# dsd01-bsta.net
KiCad netlist of a schematic drawn in EAGLE
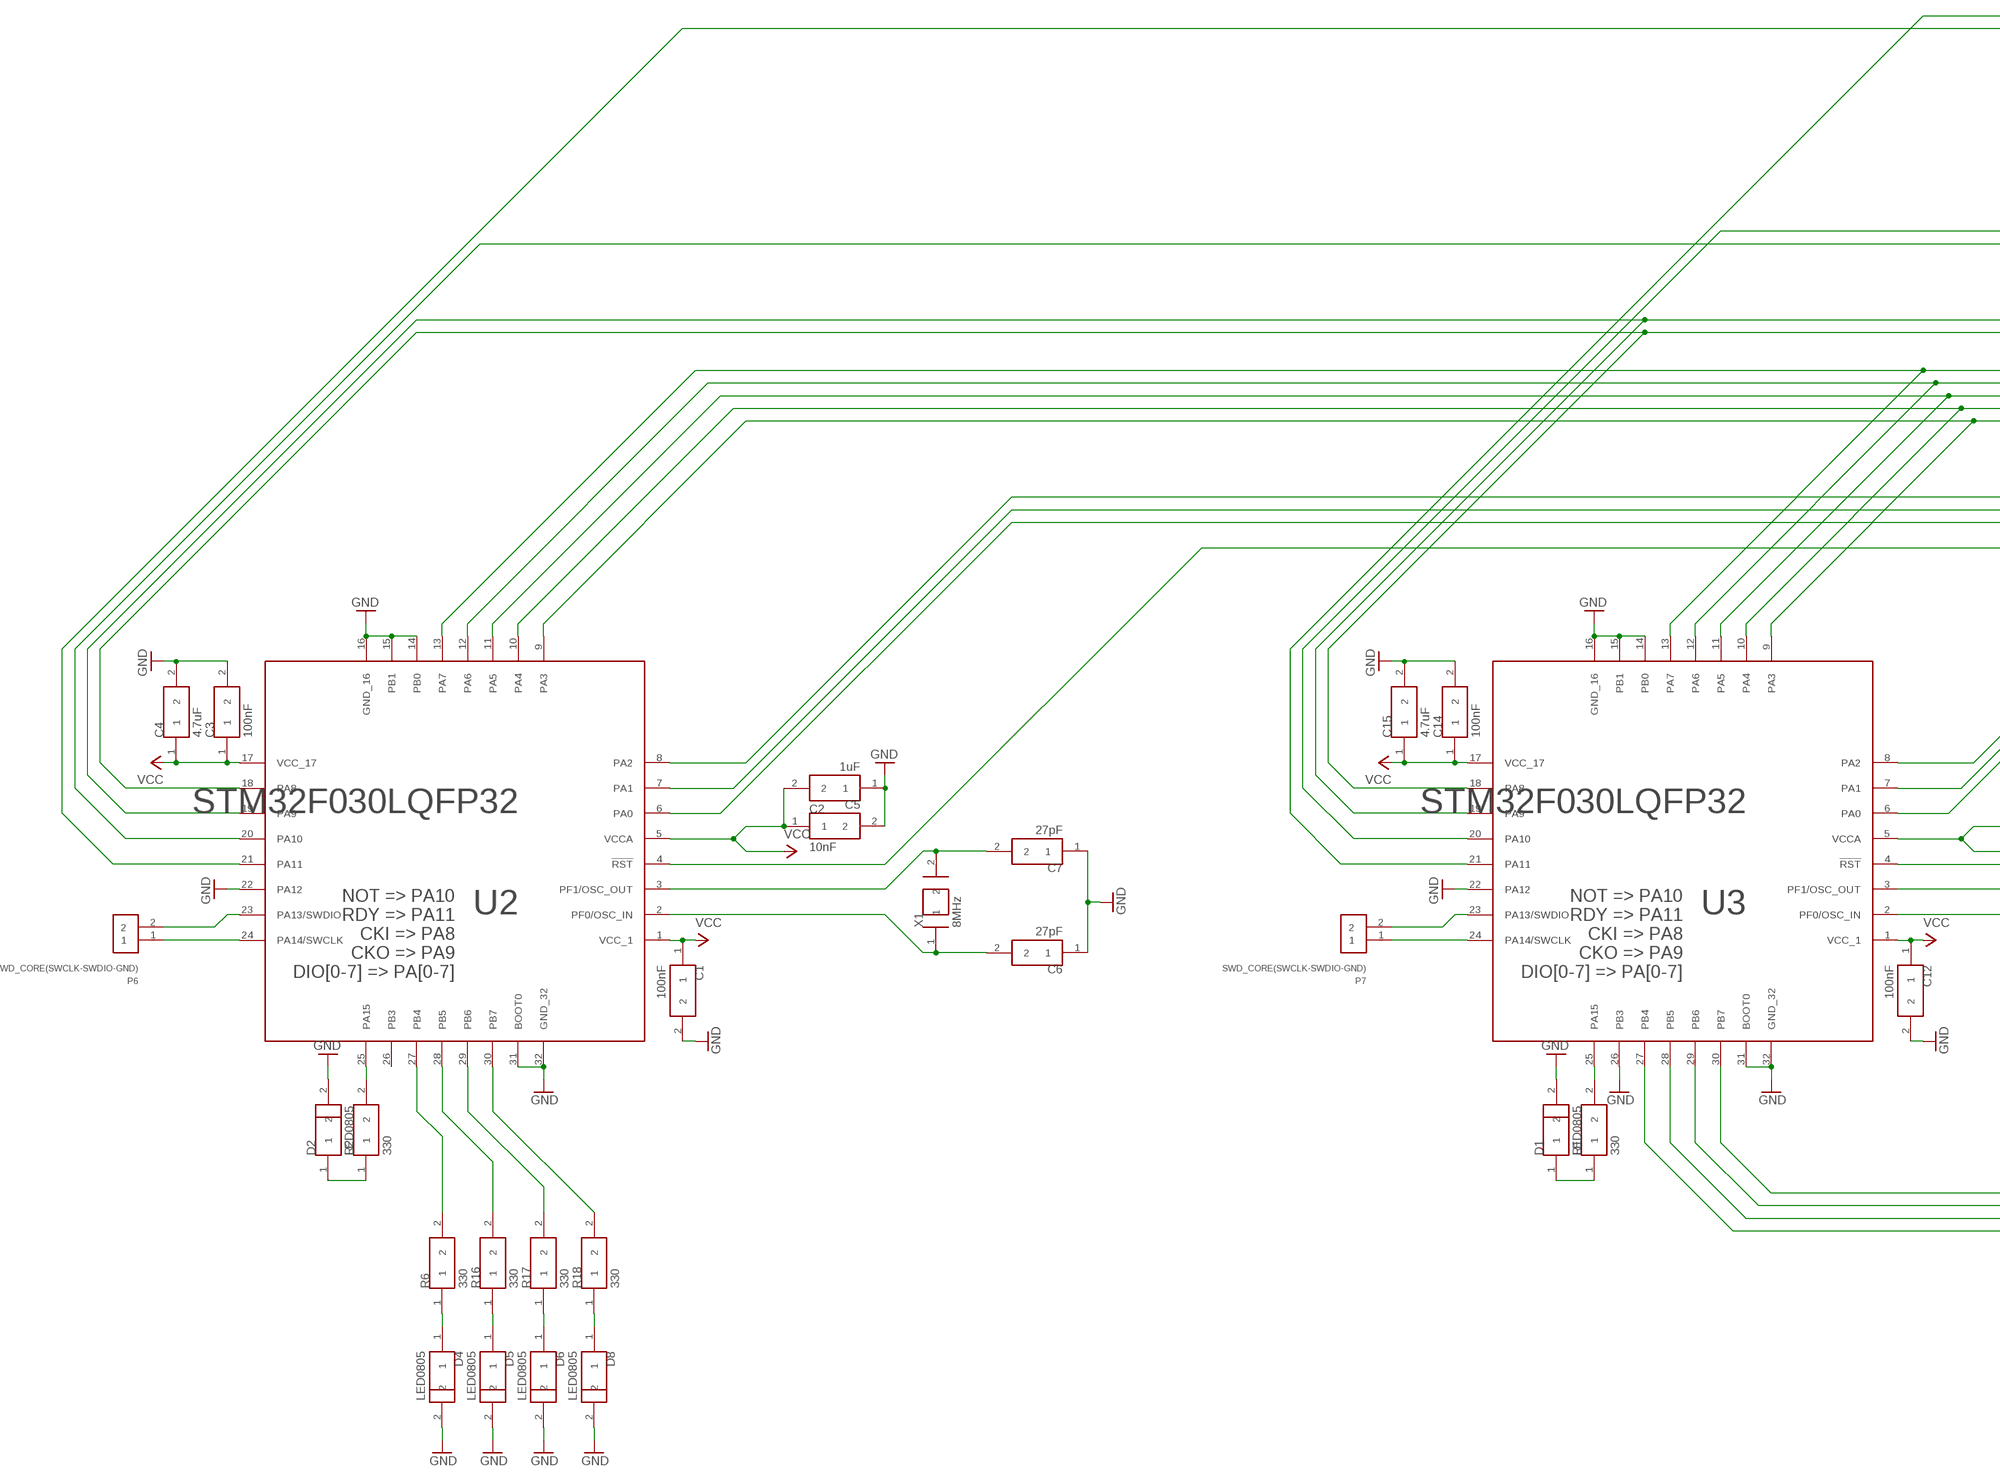
[diagram p0: schematic, sheet 1, part 1 of 2]
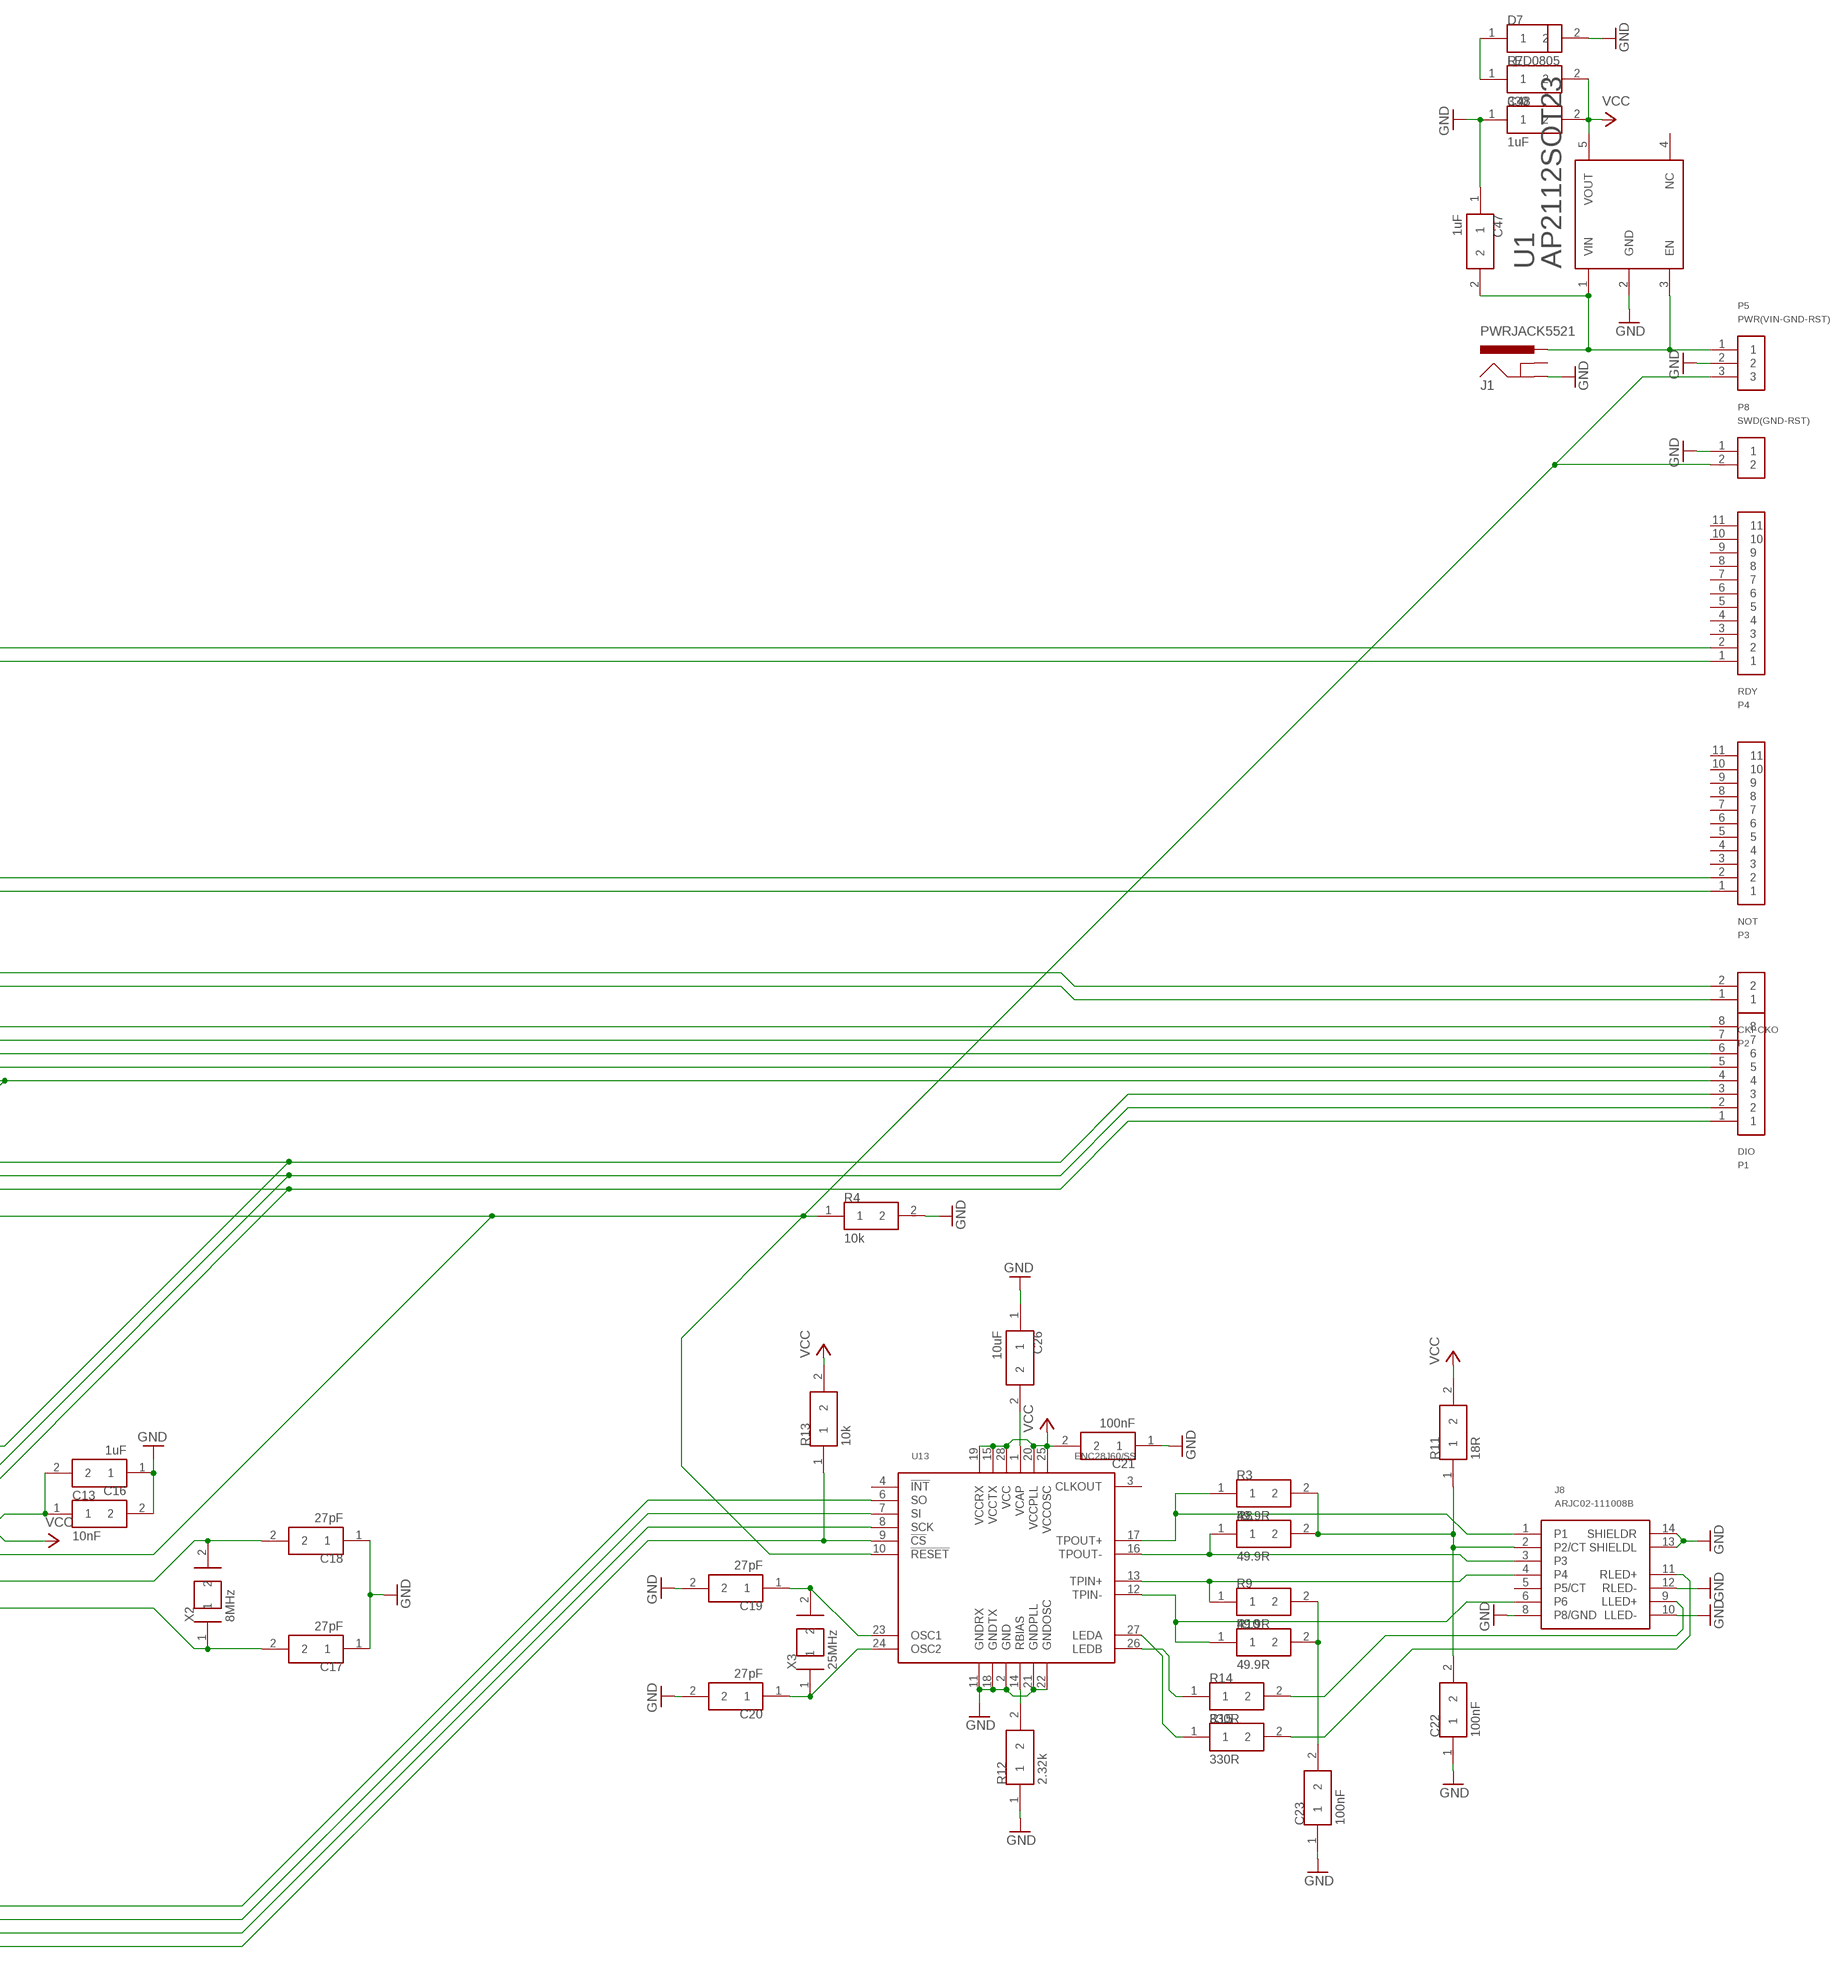
[diagram p1: schematic, sheet 1, part 2 of 2]

(export (version "E")
  (design (tool "Eeschema 10.0.6"))
  (components
    (comp (ref "C1")
      (value "100nF")
      (footprint "eagle-import:0805")
      (libsource (lib "eagle-import") (part "CAP0805"))
    )
    (comp (ref "C2")
      (value "10nF")
      (footprint "eagle-import:0805")
      (libsource (lib "eagle-import") (part "CAP0805"))
    )
    (comp (ref "C3")
      (value "100nF")
      (footprint "eagle-import:0805")
      (libsource (lib "eagle-import") (part "CAP0805"))
    )
    (comp (ref "C4")
      (value "4.7uF")
      (footprint "eagle-import:0805")
      (libsource (lib "eagle-import") (part "CAP0805"))
    )
    (comp (ref "C5")
      (value "1uF")
      (footprint "eagle-import:0805")
      (libsource (lib "eagle-import") (part "CAP0805"))
    )
    (comp (ref "C6")
      (value "27pF")
      (footprint "eagle-import:0805")
      (libsource (lib "eagle-import") (part "CAP0805"))
    )
    (comp (ref "C7")
      (value "27pF")
      (footprint "eagle-import:0805")
      (libsource (lib "eagle-import") (part "CAP0805"))
    )
    (comp (ref "C12")
      (value "100nF")
      (footprint "eagle-import:0805")
      (libsource (lib "eagle-import") (part "CAP0805"))
    )
    (comp (ref "C13")
      (value "10nF")
      (footprint "eagle-import:0805")
      (libsource (lib "eagle-import") (part "CAP0805"))
    )
    (comp (ref "C14")
      (value "100nF")
      (footprint "eagle-import:0805")
      (libsource (lib "eagle-import") (part "CAP0805"))
    )
    (comp (ref "C15")
      (value "4.7uF")
      (footprint "eagle-import:0805")
      (libsource (lib "eagle-import") (part "CAP0805"))
    )
    (comp (ref "C16")
      (value "1uF")
      (footprint "eagle-import:0805")
      (libsource (lib "eagle-import") (part "CAP0805"))
    )
    (comp (ref "C17")
      (value "27pF")
      (footprint "eagle-import:0805")
      (libsource (lib "eagle-import") (part "CAP0805"))
    )
    (comp (ref "C18")
      (value "27pF")
      (footprint "eagle-import:0805")
      (libsource (lib "eagle-import") (part "CAP0805"))
    )
    (comp (ref "C19")
      (value "27pF")
      (footprint "eagle-import:0805")
      (libsource (lib "eagle-import") (part "CAP0805"))
    )
    (comp (ref "C20")
      (value "27pF")
      (footprint "eagle-import:0805")
      (libsource (lib "eagle-import") (part "CAP0805"))
    )
    (comp (ref "C21")
      (value "100nF")
      (footprint "eagle-import:0805")
      (libsource (lib "eagle-import") (part "CAP0805"))
    )
    (comp (ref "C22")
      (value "100nF")
      (footprint "eagle-import:0805")
      (libsource (lib "eagle-import") (part "CAP0805"))
    )
    (comp (ref "C23")
      (value "100nF")
      (footprint "eagle-import:0805")
      (libsource (lib "eagle-import") (part "CAP0805"))
    )
    (comp (ref "C26")
      (value "10uF")
      (footprint "eagle-import:0805")
      (libsource (lib "eagle-import") (part "CAP0805"))
    )
    (comp (ref "C47")
      (value "1uF")
      (footprint "eagle-import:0805")
      (libsource (lib "eagle-import") (part "CAP0805"))
    )
    (comp (ref "C48")
      (value "1uF")
      (footprint "eagle-import:0805")
      (libsource (lib "eagle-import") (part "CAP0805"))
    )
    (comp (ref "D1")
      (value "LED0805")
      (footprint "eagle-import:0805")
      (libsource (lib "eagle-import") (part "LED0805"))
    )
    (comp (ref "D2")
      (value "LED0805")
      (footprint "eagle-import:0805")
      (libsource (lib "eagle-import") (part "LED0805"))
    )
    (comp (ref "D4")
      (value "LED0805")
      (footprint "eagle-import:0805")
      (libsource (lib "eagle-import") (part "LED0805"))
    )
    (comp (ref "D5")
      (value "LED0805")
      (footprint "eagle-import:0805")
      (libsource (lib "eagle-import") (part "LED0805"))
    )
    (comp (ref "D6")
      (value "LED0805")
      (footprint "eagle-import:0805")
      (libsource (lib "eagle-import") (part "LED0805"))
    )
    (comp (ref "D7")
      (value "LED0805")
      (footprint "eagle-import:0805")
      (libsource (lib "eagle-import") (part "LED0805"))
    )
    (comp (ref "D8")
      (value "LED0805")
      (footprint "eagle-import:0805")
      (libsource (lib "eagle-import") (part "LED0805"))
    )
    (comp (ref "J1")
      (value "PWRJACK5521")
      (footprint "eagle-import:PWRJACK_5521")
      (libsource (lib "eagle-import") (part "PWRJACK5521"))
    )
    (comp (ref "J8")
      (value "ARJC02-111008B")
      (footprint "eagle-import:ARJC02-111008B")
      (libsource (lib "eagle-import") (part "ARJC02-111008B"))
    )
    (comp (ref "P1")
      (value "DIO")
      (footprint "eagle-import:PIN_8")
      (libsource (lib "eagle-import") (part "PIN_8"))
    )
    (comp (ref "P2")
      (value "CKI-CKO")
      (footprint "eagle-import:PIN_2")
      (libsource (lib "eagle-import") (part "PIN_2"))
    )
    (comp (ref "P3")
      (value "NOT")
      (footprint "eagle-import:PIN_11")
      (libsource (lib "eagle-import") (part "PIN_11"))
    )
    (comp (ref "P4")
      (value "RDY")
      (footprint "eagle-import:PIN_11")
      (libsource (lib "eagle-import") (part "PIN_11"))
    )
    (comp (ref "P5")
      (value "PWR(VIN-GND-RST)")
      (footprint "eagle-import:PIN_3")
      (libsource (lib "eagle-import") (part "PIN_3"))
    )
    (comp (ref "P6")
      (value "SWD_CORE(SWCLK-SWDIO-GND)")
      (footprint "eagle-import:PIN_2")
      (libsource (lib "eagle-import") (part "PIN_2"))
    )
    (comp (ref "P7")
      (value "SWD_CORE(SWCLK-SWDIO-GND)")
      (footprint "eagle-import:PIN_2")
      (libsource (lib "eagle-import") (part "PIN_2"))
    )
    (comp (ref "P8")
      (value "SWD(GND-RST)")
      (footprint "eagle-import:PIN_2")
      (libsource (lib "eagle-import") (part "PIN_2"))
    )
    (comp (ref "R1")
      (value "330")
      (footprint "eagle-import:0805")
      (libsource (lib "eagle-import") (part "RES0805"))
    )
    (comp (ref "R2")
      (value "330")
      (footprint "eagle-import:0805")
      (libsource (lib "eagle-import") (part "RES0805"))
    )
    (comp (ref "R3")
      (value "49.9R")
      (footprint "eagle-import:0805")
      (libsource (lib "eagle-import") (part "RES0805"))
    )
    (comp (ref "R4")
      (value "10k")
      (footprint "eagle-import:0805")
      (libsource (lib "eagle-import") (part "RES0805"))
    )
    (comp (ref "R6")
      (value "330")
      (footprint "eagle-import:0805")
      (libsource (lib "eagle-import") (part "RES0805"))
    )
    (comp (ref "R7")
      (value "330")
      (footprint "eagle-import:0805")
      (libsource (lib "eagle-import") (part "RES0805"))
    )
    (comp (ref "R8")
      (value "49.9R")
      (footprint "eagle-import:0805")
      (libsource (lib "eagle-import") (part "RES0805"))
    )
    (comp (ref "R9")
      (value "49.9R")
      (footprint "eagle-import:0805")
      (libsource (lib "eagle-import") (part "RES0805"))
    )
    (comp (ref "R10")
      (value "49.9R")
      (footprint "eagle-import:0805")
      (libsource (lib "eagle-import") (part "RES0805"))
    )
    (comp (ref "R11")
      (value "18R")
      (footprint "eagle-import:0805")
      (libsource (lib "eagle-import") (part "RES0805"))
    )
    (comp (ref "R12")
      (value "2.32k")
      (footprint "eagle-import:0805")
      (libsource (lib "eagle-import") (part "RES0805"))
    )
    (comp (ref "R13")
      (value "10k")
      (footprint "eagle-import:0805")
      (libsource (lib "eagle-import") (part "RES0805"))
    )
    (comp (ref "R14")
      (value "330R")
      (footprint "eagle-import:0805")
      (libsource (lib "eagle-import") (part "RES0805"))
    )
    (comp (ref "R15")
      (value "330R")
      (footprint "eagle-import:0805")
      (libsource (lib "eagle-import") (part "RES0805"))
    )
    (comp (ref "R16")
      (value "330")
      (footprint "eagle-import:0805")
      (libsource (lib "eagle-import") (part "RES0805"))
    )
    (comp (ref "R17")
      (value "330")
      (footprint "eagle-import:0805")
      (libsource (lib "eagle-import") (part "RES0805"))
    )
    (comp (ref "R18")
      (value "330")
      (footprint "eagle-import:0805")
      (libsource (lib "eagle-import") (part "RES0805"))
    )
    (comp (ref "U1")
      (value "AP2112SOT23")
      (footprint "eagle-import:SOT23-5")
      (libsource (lib "eagle-import") (part "AP2112SOT23"))
    )
    (comp (ref "U2")
      (value "STM32F030LQFP32")
      (footprint "eagle-import:QFP32")
      (libsource (lib "eagle-import") (part "STM32F030LQFP32"))
    )
    (comp (ref "U3")
      (value "STM32F030LQFP32")
      (footprint "eagle-import:QFP32")
      (libsource (lib "eagle-import") (part "STM32F030LQFP32"))
    )
    (comp (ref "U13")
      (value "ENC28J60/SS")
      (footprint "eagle-import:SSOP28")
      (libsource (lib "eagle-import") (part "ENC28J60/SS"))
    )
    (comp (ref "X1")
      (value "8MHz")
      (footprint "eagle-import:XTAL_532")
      (libsource (lib "eagle-import") (part "XTALSMD-5X32"))
    )
    (comp (ref "X2")
      (value "8MHz")
      (footprint "eagle-import:XTAL_532")
      (libsource (lib "eagle-import") (part "XTALSMD-5X32"))
    )
    (comp (ref "X3")
      (value "25MHz")
      (footprint "eagle-import:XTAL_532")
      (libsource (lib "eagle-import") (part "XTALSMD-5X32"))
    )
  )
  (nets
    (net (code "1") (name "GND") (class "Default")
      (node (ref "C1") (pin "2") (pinfunction "2_2") (pintype "bidirectional"))
      (node (ref "C12") (pin "2") (pinfunction "2_2") (pintype "bidirectional"))
      (node (ref "C13") (pin "2") (pinfunction "2_2") (pintype "bidirectional"))
      (node (ref "C14") (pin "2") (pinfunction "2_2") (pintype "bidirectional"))
      (node (ref "C15") (pin "2") (pinfunction "2_2") (pintype "bidirectional"))
      (node (ref "C16") (pin "1") (pinfunction "1_1") (pintype "bidirectional"))
      (node (ref "C17") (pin "1") (pinfunction "1_1") (pintype "bidirectional"))
      (node (ref "C18") (pin "1") (pinfunction "1_1") (pintype "bidirectional"))
      (node (ref "C19") (pin "2") (pinfunction "2_2") (pintype "bidirectional"))
      (node (ref "C2") (pin "2") (pinfunction "2_2") (pintype "bidirectional"))
      (node (ref "C20") (pin "2") (pinfunction "2_2") (pintype "bidirectional"))
      (node (ref "C21") (pin "1") (pinfunction "1_1") (pintype "bidirectional"))
      (node (ref "C22") (pin "1") (pinfunction "1_1") (pintype "bidirectional"))
      (node (ref "C23") (pin "1") (pinfunction "1_1") (pintype "bidirectional"))
      (node (ref "C26") (pin "1") (pinfunction "1_1") (pintype "bidirectional"))
      (node (ref "C3") (pin "2") (pinfunction "2_2") (pintype "bidirectional"))
      (node (ref "C4") (pin "2") (pinfunction "2_2") (pintype "bidirectional"))
      (node (ref "C47") (pin "1") (pinfunction "1_1") (pintype "bidirectional"))
      (node (ref "C48") (pin "1") (pinfunction "1_1") (pintype "bidirectional"))
      (node (ref "C5") (pin "1") (pinfunction "1_1") (pintype "bidirectional"))
      (node (ref "C6") (pin "1") (pinfunction "1_1") (pintype "bidirectional"))
      (node (ref "C7") (pin "1") (pinfunction "1_1") (pintype "bidirectional"))
      (node (ref "D1") (pin "2") (pinfunction "2_2") (pintype "bidirectional"))
      (node (ref "D2") (pin "2") (pinfunction "2_2") (pintype "bidirectional"))
      (node (ref "D4") (pin "2") (pinfunction "2_2") (pintype "bidirectional"))
      (node (ref "D5") (pin "2") (pinfunction "2_2") (pintype "bidirectional"))
      (node (ref "D6") (pin "2") (pinfunction "2_2") (pintype "bidirectional"))
      (node (ref "D7") (pin "2") (pinfunction "2_2") (pintype "bidirectional"))
      (node (ref "D8") (pin "2") (pinfunction "2_2") (pintype "bidirectional"))
      (node (ref "J1") (pin "GND") (pinfunction "GND_GND") (pintype "bidirectional"))
      (node (ref "J8") (pin "10") (pinfunction "LLED-_10") (pintype "bidirectional"))
      (node (ref "J8") (pin "12") (pinfunction "RLED-_12") (pintype "bidirectional"))
      (node (ref "J8") (pin "13") (pinfunction "SHIELDL_13") (pintype "bidirectional"))
      (node (ref "J8") (pin "14") (pinfunction "SHIELDR_14") (pintype "bidirectional"))
      (node (ref "J8") (pin "8") (pinfunction "P8/GND_8") (pintype "bidirectional"))
      (node (ref "P5") (pin "2") (pinfunction "2_2") (pintype "bidirectional"))
      (node (ref "P8") (pin "1") (pinfunction "1_1") (pintype "bidirectional"))
      (node (ref "R12") (pin "1") (pinfunction "1_1") (pintype "bidirectional"))
      (node (ref "R4") (pin "2") (pinfunction "2_2") (pintype "bidirectional"))
      (node (ref "U1") (pin "2") (pinfunction "GND_2") (pintype "bidirectional"))
      (node (ref "U13") (pin "11") (pinfunction "GNDRX_11") (pintype "bidirectional"))
      (node (ref "U13") (pin "18") (pinfunction "GNDTX_18") (pintype "bidirectional"))
      (node (ref "U13") (pin "2") (pinfunction "GND_2") (pintype "bidirectional"))
      (node (ref "U13") (pin "21") (pinfunction "GNDPLL_21") (pintype "bidirectional"))
      (node (ref "U13") (pin "22") (pinfunction "GNDOSC_22") (pintype "bidirectional"))
      (node (ref "U2") (pin "14") (pinfunction "PB0_14") (pintype "bidirectional"))
      (node (ref "U2") (pin "15") (pinfunction "PB1_15") (pintype "bidirectional"))
      (node (ref "U2") (pin "16") (pinfunction "GND_16_16") (pintype "bidirectional"))
      (node (ref "U2") (pin "22") (pinfunction "PA12_22") (pintype "bidirectional"))
      (node (ref "U2") (pin "31") (pinfunction "BOOT0_31") (pintype "bidirectional"))
      (node (ref "U2") (pin "32") (pinfunction "GND_32_32") (pintype "bidirectional"))
      (node (ref "U3") (pin "14") (pinfunction "PB0_14") (pintype "bidirectional"))
      (node (ref "U3") (pin "15") (pinfunction "PB1_15") (pintype "bidirectional"))
      (node (ref "U3") (pin "16") (pinfunction "GND_16_16") (pintype "bidirectional"))
      (node (ref "U3") (pin "22") (pinfunction "PA12_22") (pintype "bidirectional"))
      (node (ref "U3") (pin "26") (pinfunction "PB3_26") (pintype "bidirectional"))
      (node (ref "U3") (pin "31") (pinfunction "BOOT0_31") (pintype "bidirectional"))
      (node (ref "U3") (pin "32") (pinfunction "GND_32_32") (pintype "bidirectional"))
    )
    (net (code "2") (name "Net-(C23-Pad2)") (class "Default")
      (node (ref "C23") (pin "2") (pinfunction "2_2") (pintype "bidirectional"))
      (node (ref "R10") (pin "2") (pinfunction "2_2") (pintype "bidirectional"))
      (node (ref "R9") (pin "2") (pinfunction "2_2") (pintype "bidirectional"))
    )
    (net (code "3") (name "Net-(D1-Pad1)") (class "Default")
      (node (ref "D1") (pin "1") (pinfunction "1_1") (pintype "bidirectional"))
      (node (ref "R1") (pin "1") (pinfunction "1_1") (pintype "bidirectional"))
    )
    (net (code "4") (name "Net-(D2-Pad1)") (class "Default")
      (node (ref "D2") (pin "1") (pinfunction "1_1") (pintype "bidirectional"))
      (node (ref "R2") (pin "1") (pinfunction "1_1") (pintype "bidirectional"))
    )
    (net (code "5") (name "Net-(D4-Pad1)") (class "Default")
      (node (ref "D4") (pin "1") (pinfunction "1_1") (pintype "bidirectional"))
      (node (ref "R6") (pin "1") (pinfunction "1_1") (pintype "bidirectional"))
    )
    (net (code "6") (name "Net-(D5-Pad1)") (class "Default")
      (node (ref "D5") (pin "1") (pinfunction "1_1") (pintype "bidirectional"))
      (node (ref "R16") (pin "1") (pinfunction "1_1") (pintype "bidirectional"))
    )
    (net (code "7") (name "Net-(D6-Pad1)") (class "Default")
      (node (ref "D6") (pin "1") (pinfunction "1_1") (pintype "bidirectional"))
      (node (ref "R17") (pin "1") (pinfunction "1_1") (pintype "bidirectional"))
    )
    (net (code "8") (name "Net-(D7-Pad1)") (class "Default")
      (node (ref "D7") (pin "1") (pinfunction "1_1") (pintype "bidirectional"))
      (node (ref "R7") (pin "1") (pinfunction "1_1") (pintype "bidirectional"))
    )
    (net (code "9") (name "Net-(D8-Pad1)") (class "Default")
      (node (ref "D8") (pin "1") (pinfunction "1_1") (pintype "bidirectional"))
      (node (ref "R18") (pin "1") (pinfunction "1_1") (pintype "bidirectional"))
    )
    (net (code "10") (name "Net-(J8-LLED+)") (class "Default")
      (node (ref "J8") (pin "9") (pinfunction "LLED+_9") (pintype "bidirectional"))
      (node (ref "R14") (pin "2") (pinfunction "2_2") (pintype "bidirectional"))
    )
    (net (code "11") (name "Net-(J8-P1)") (class "Default")
      (node (ref "J8") (pin "1") (pinfunction "P1_1") (pintype "bidirectional"))
      (node (ref "R3") (pin "1") (pinfunction "1_1") (pintype "bidirectional"))
      (node (ref "U13") (pin "17") (pinfunction "TPOUT+_17") (pintype "bidirectional"))
    )
    (net (code "12") (name "Net-(J8-P2{slash}CT)") (class "Default")
      (node (ref "C22") (pin "2") (pinfunction "2_2") (pintype "bidirectional"))
      (node (ref "J8") (pin "2") (pinfunction "P2/CT_2") (pintype "bidirectional"))
      (node (ref "R11") (pin "1") (pinfunction "1_1") (pintype "bidirectional"))
      (node (ref "R3") (pin "2") (pinfunction "2_2") (pintype "bidirectional"))
      (node (ref "R8") (pin "2") (pinfunction "2_2") (pintype "bidirectional"))
    )
    (net (code "13") (name "Net-(J8-P3)") (class "Default")
      (node (ref "J8") (pin "3") (pinfunction "P3_3") (pintype "bidirectional"))
      (node (ref "R8") (pin "1") (pinfunction "1_1") (pintype "bidirectional"))
      (node (ref "U13") (pin "16") (pinfunction "TPOUT-_16") (pintype "bidirectional"))
    )
    (net (code "14") (name "Net-(J8-P4)") (class "Default")
      (node (ref "J8") (pin "4") (pinfunction "P4_4") (pintype "bidirectional"))
      (node (ref "R9") (pin "1") (pinfunction "1_1") (pintype "bidirectional"))
      (node (ref "U13") (pin "13") (pinfunction "TPIN+_13") (pintype "bidirectional"))
    )
    (net (code "15") (name "Net-(J8-P6)") (class "Default")
      (node (ref "J8") (pin "6") (pinfunction "P6_6") (pintype "bidirectional"))
      (node (ref "R10") (pin "1") (pinfunction "1_1") (pintype "bidirectional"))
      (node (ref "U13") (pin "12") (pinfunction "TPIN-_12") (pintype "bidirectional"))
    )
    (net (code "16") (name "Net-(J8-RLED+)") (class "Default")
      (node (ref "J8") (pin "11") (pinfunction "RLED+_11") (pintype "bidirectional"))
      (node (ref "R15") (pin "2") (pinfunction "2_2") (pintype "bidirectional"))
    )
    (net (code "17") (name "Net-(U1-EN)") (class "Default")
      (node (ref "C47") (pin "2") (pinfunction "2_2") (pintype "bidirectional"))
      (node (ref "J1") (pin "PWR") (pinfunction "PWR_PWR") (pintype "bidirectional"))
      (node (ref "P5") (pin "1") (pinfunction "1_1") (pintype "bidirectional"))
      (node (ref "U1") (pin "1") (pinfunction "VIN_1") (pintype "bidirectional"))
      (node (ref "U1") (pin "3") (pinfunction "EN_3") (pintype "bidirectional"))
    )
    (net (code "18") (name "Net-(U2-PA0)") (class "Default")
      (node (ref "P1") (pin "1") (pinfunction "1_1") (pintype "bidirectional"))
      (node (ref "U2") (pin "6") (pinfunction "PA0_6") (pintype "bidirectional"))
      (node (ref "U3") (pin "6") (pinfunction "PA0_6") (pintype "bidirectional"))
    )
    (net (code "19") (name "Net-(U2-PA1)") (class "Default")
      (node (ref "P1") (pin "2") (pinfunction "2_2") (pintype "bidirectional"))
      (node (ref "U2") (pin "7") (pinfunction "PA1_7") (pintype "bidirectional"))
      (node (ref "U3") (pin "7") (pinfunction "PA1_7") (pintype "bidirectional"))
    )
    (net (code "20") (name "Net-(U2-PA2)") (class "Default")
      (node (ref "P1") (pin "3") (pinfunction "3_3") (pintype "bidirectional"))
      (node (ref "U2") (pin "8") (pinfunction "PA2_8") (pintype "bidirectional"))
      (node (ref "U3") (pin "8") (pinfunction "PA2_8") (pintype "bidirectional"))
    )
    (net (code "21") (name "Net-(U2-PA3)") (class "Default")
      (node (ref "P1") (pin "4") (pinfunction "4_4") (pintype "bidirectional"))
      (node (ref "U2") (pin "9") (pinfunction "PA3_9") (pintype "bidirectional"))
      (node (ref "U3") (pin "9") (pinfunction "PA3_9") (pintype "bidirectional"))
    )
    (net (code "22") (name "Net-(U2-PA4)") (class "Default")
      (node (ref "P1") (pin "5") (pinfunction "5_5") (pintype "bidirectional"))
      (node (ref "U2") (pin "10") (pinfunction "PA4_10") (pintype "bidirectional"))
      (node (ref "U3") (pin "10") (pinfunction "PA4_10") (pintype "bidirectional"))
    )
    (net (code "23") (name "Net-(U2-PA5)") (class "Default")
      (node (ref "P1") (pin "6") (pinfunction "6_6") (pintype "bidirectional"))
      (node (ref "U2") (pin "11") (pinfunction "PA5_11") (pintype "bidirectional"))
      (node (ref "U3") (pin "11") (pinfunction "PA5_11") (pintype "bidirectional"))
    )
    (net (code "24") (name "Net-(U2-PA6)") (class "Default")
      (node (ref "P1") (pin "7") (pinfunction "7_7") (pintype "bidirectional"))
      (node (ref "U2") (pin "12") (pinfunction "PA6_12") (pintype "bidirectional"))
      (node (ref "U3") (pin "12") (pinfunction "PA6_12") (pintype "bidirectional"))
    )
    (net (code "25") (name "Net-(U2-PA7)") (class "Default")
      (node (ref "P1") (pin "8") (pinfunction "8_8") (pintype "bidirectional"))
      (node (ref "U2") (pin "13") (pinfunction "PA7_13") (pintype "bidirectional"))
      (node (ref "U3") (pin "13") (pinfunction "PA7_13") (pintype "bidirectional"))
    )
    (net (code "26") (name "Net-(U2-PA8)") (class "Default")
      (node (ref "P2") (pin "1") (pinfunction "1_1") (pintype "bidirectional"))
      (node (ref "U2") (pin "18") (pinfunction "PA8_18") (pintype "bidirectional"))
      (node (ref "U3") (pin "18") (pinfunction "PA8_18") (pintype "bidirectional"))
    )
    (net (code "27") (name "Net-(U2-PA9)") (class "Default")
      (node (ref "P2") (pin "2") (pinfunction "2_2") (pintype "bidirectional"))
      (node (ref "U2") (pin "19") (pinfunction "PA9_19") (pintype "bidirectional"))
      (node (ref "U3") (pin "19") (pinfunction "PA9_19") (pintype "bidirectional"))
    )
    (net (code "28") (name "Net-(U2-PA10)") (class "Default")
      (node (ref "P3") (pin "1") (pinfunction "1_1") (pintype "bidirectional"))
      (node (ref "U2") (pin "20") (pinfunction "PA10_20") (pintype "bidirectional"))
    )
    (net (code "29") (name "Net-(U2-PA11)") (class "Default")
      (node (ref "P4") (pin "1") (pinfunction "1_1") (pintype "bidirectional"))
      (node (ref "U2") (pin "21") (pinfunction "PA11_21") (pintype "bidirectional"))
    )
    (net (code "30") (name "Net-(U2-PA13{slash}SWDIO)") (class "Default")
      (node (ref "P6") (pin "2") (pinfunction "2_2") (pintype "bidirectional"))
      (node (ref "U2") (pin "23") (pinfunction "PA13/SWDIO_23") (pintype "bidirectional"))
    )
    (net (code "31") (name "Net-(U2-PA14{slash}SWCLK)") (class "Default")
      (node (ref "P6") (pin "1") (pinfunction "1_1") (pintype "bidirectional"))
      (node (ref "U2") (pin "24") (pinfunction "PA14/SWCLK_24") (pintype "bidirectional"))
    )
    (net (code "32") (name "Net-(U2-PA15)") (class "Default")
      (node (ref "R2") (pin "2") (pinfunction "2_2") (pintype "bidirectional"))
      (node (ref "U2") (pin "25") (pinfunction "PA15_25") (pintype "bidirectional"))
    )
    (net (code "33") (name "Net-(U2-PB4)") (class "Default")
      (node (ref "R6") (pin "2") (pinfunction "2_2") (pintype "bidirectional"))
      (node (ref "U2") (pin "27") (pinfunction "PB4_27") (pintype "bidirectional"))
    )
    (net (code "34") (name "Net-(U2-PB5)") (class "Default")
      (node (ref "R16") (pin "2") (pinfunction "2_2") (pintype "bidirectional"))
      (node (ref "U2") (pin "28") (pinfunction "PB5_28") (pintype "bidirectional"))
    )
    (net (code "35") (name "Net-(U2-PB6)") (class "Default")
      (node (ref "R17") (pin "2") (pinfunction "2_2") (pintype "bidirectional"))
      (node (ref "U2") (pin "29") (pinfunction "PB6_29") (pintype "bidirectional"))
    )
    (net (code "36") (name "Net-(U2-PB7)") (class "Default")
      (node (ref "R18") (pin "2") (pinfunction "2_2") (pintype "bidirectional"))
      (node (ref "U2") (pin "30") (pinfunction "PB7_30") (pintype "bidirectional"))
    )
    (net (code "37") (name "Net-(U2-PF0{slash}OSC_IN)") (class "Default")
      (node (ref "C6") (pin "2") (pinfunction "2_2") (pintype "bidirectional"))
      (node (ref "U2") (pin "2") (pinfunction "PF0/OSC_IN_2") (pintype "bidirectional"))
      (node (ref "X1") (pin "1") (pinfunction "1_1") (pintype "bidirectional"))
    )
    (net (code "38") (name "Net-(U2-PF1{slash}OSC_OUT)") (class "Default")
      (node (ref "C7") (pin "2") (pinfunction "2_2") (pintype "bidirectional"))
      (node (ref "U2") (pin "3") (pinfunction "PF1/OSC_OUT_3") (pintype "bidirectional"))
      (node (ref "X1") (pin "2") (pinfunction "2_2") (pintype "bidirectional"))
    )
    (net (code "39") (name "Net-(U3-PA10)") (class "Default")
      (node (ref "P3") (pin "2") (pinfunction "2_2") (pintype "bidirectional"))
      (node (ref "U3") (pin "20") (pinfunction "PA10_20") (pintype "bidirectional"))
    )
    (net (code "40") (name "Net-(U3-PA11)") (class "Default")
      (node (ref "P4") (pin "2") (pinfunction "2_2") (pintype "bidirectional"))
      (node (ref "U3") (pin "21") (pinfunction "PA11_21") (pintype "bidirectional"))
    )
    (net (code "41") (name "Net-(U3-PA13{slash}SWDIO)") (class "Default")
      (node (ref "P7") (pin "2") (pinfunction "2_2") (pintype "bidirectional"))
      (node (ref "U3") (pin "23") (pinfunction "PA13/SWDIO_23") (pintype "bidirectional"))
    )
    (net (code "42") (name "Net-(U3-PA14{slash}SWCLK)") (class "Default")
      (node (ref "P7") (pin "1") (pinfunction "1_1") (pintype "bidirectional"))
      (node (ref "U3") (pin "24") (pinfunction "PA14/SWCLK_24") (pintype "bidirectional"))
    )
    (net (code "43") (name "Net-(U3-PA15)") (class "Default")
      (node (ref "R1") (pin "2") (pinfunction "2_2") (pintype "bidirectional"))
      (node (ref "U3") (pin "25") (pinfunction "PA15_25") (pintype "bidirectional"))
    )
    (net (code "44") (name "Net-(U3-PF0{slash}OSC_IN)") (class "Default")
      (node (ref "C17") (pin "2") (pinfunction "2_2") (pintype "bidirectional"))
      (node (ref "U3") (pin "2") (pinfunction "PF0/OSC_IN_2") (pintype "bidirectional"))
      (node (ref "X2") (pin "1") (pinfunction "1_1") (pintype "bidirectional"))
    )
    (net (code "45") (name "Net-(U3-PF1{slash}OSC_OUT)") (class "Default")
      (node (ref "C18") (pin "2") (pinfunction "2_2") (pintype "bidirectional"))
      (node (ref "U3") (pin "3") (pinfunction "PF1/OSC_OUT_3") (pintype "bidirectional"))
      (node (ref "X2") (pin "2") (pinfunction "2_2") (pintype "bidirectional"))
    )
    (net (code "46") (name "Net-(U13-LEDA)") (class "Default")
      (node (ref "R15") (pin "1") (pinfunction "1_1") (pintype "bidirectional"))
      (node (ref "U13") (pin "27") (pinfunction "LEDA_27") (pintype "bidirectional"))
    )
    (net (code "47") (name "Net-(U13-LEDB)") (class "Default")
      (node (ref "R14") (pin "1") (pinfunction "1_1") (pintype "bidirectional"))
      (node (ref "U13") (pin "26") (pinfunction "LEDB_26") (pintype "bidirectional"))
    )
    (net (code "48") (name "Net-(U13-OSC1)") (class "Default")
      (node (ref "C19") (pin "1") (pinfunction "1_1") (pintype "bidirectional"))
      (node (ref "U13") (pin "23") (pinfunction "OSC1_23") (pintype "bidirectional"))
      (node (ref "X3") (pin "2") (pinfunction "2_2") (pintype "bidirectional"))
    )
    (net (code "49") (name "Net-(U13-OSC2)") (class "Default")
      (node (ref "C20") (pin "1") (pinfunction "1_1") (pintype "bidirectional"))
      (node (ref "U13") (pin "24") (pinfunction "OSC2_24") (pintype "bidirectional"))
      (node (ref "X3") (pin "1") (pinfunction "1_1") (pintype "bidirectional"))
    )
    (net (code "50") (name "Net-(U13-RBIAS)") (class "Default")
      (node (ref "R12") (pin "2") (pinfunction "2_2") (pintype "bidirectional"))
      (node (ref "U13") (pin "14") (pinfunction "RBIAS_14") (pintype "bidirectional"))
    )
    (net (code "51") (name "Net-(U13-SCK)") (class "Default")
      (node (ref "U13") (pin "8") (pinfunction "SCK_8") (pintype "bidirectional"))
      (node (ref "U3") (pin "28") (pinfunction "PB5_28") (pintype "bidirectional"))
    )
    (net (code "52") (name "Net-(U13-SI)") (class "Default")
      (node (ref "U13") (pin "7") (pinfunction "SI_7") (pintype "bidirectional"))
      (node (ref "U3") (pin "29") (pinfunction "PB6_29") (pintype "bidirectional"))
    )
    (net (code "53") (name "Net-(U13-SO)") (class "Default")
      (node (ref "U13") (pin "6") (pinfunction "SO_6") (pintype "bidirectional"))
      (node (ref "U3") (pin "30") (pinfunction "PB7_30") (pintype "bidirectional"))
    )
    (net (code "54") (name "Net-(U13-VCAP)") (class "Default")
      (node (ref "C26") (pin "2") (pinfunction "2_2") (pintype "bidirectional"))
      (node (ref "U13") (pin "1") (pinfunction "VCAP_1") (pintype "bidirectional"))
    )
    (net (code "55") (name "Net-(U13-~{CS})") (class "Default")
      (node (ref "R13") (pin "1") (pinfunction "1_1") (pintype "bidirectional"))
      (node (ref "U13") (pin "9") (pinfunction "~{CS}_9") (pintype "bidirectional"))
      (node (ref "U3") (pin "27") (pinfunction "PB4_27") (pintype "bidirectional"))
    )
    (net (code "56") (name "Net-(U13-~{RESET})") (class "Default")
      (node (ref "P5") (pin "3") (pinfunction "3_3") (pintype "bidirectional"))
      (node (ref "P8") (pin "2") (pinfunction "2_2") (pintype "bidirectional"))
      (node (ref "R4") (pin "1") (pinfunction "1_1") (pintype "bidirectional"))
      (node (ref "U13") (pin "10") (pinfunction "~{RESET}_10") (pintype "bidirectional"))
      (node (ref "U2") (pin "4") (pinfunction "~{RST}_4") (pintype "bidirectional"))
      (node (ref "U3") (pin "4") (pinfunction "~{RST}_4") (pintype "bidirectional"))
    )
    (net (code "57") (name "VCC") (class "Default")
      (node (ref "C1") (pin "1") (pinfunction "1_1") (pintype "bidirectional"))
      (node (ref "C12") (pin "1") (pinfunction "1_1") (pintype "bidirectional"))
      (node (ref "C13") (pin "1") (pinfunction "1_1") (pintype "bidirectional"))
      (node (ref "C14") (pin "1") (pinfunction "1_1") (pintype "bidirectional"))
      (node (ref "C15") (pin "1") (pinfunction "1_1") (pintype "bidirectional"))
      (node (ref "C16") (pin "2") (pinfunction "2_2") (pintype "bidirectional"))
      (node (ref "C2") (pin "1") (pinfunction "1_1") (pintype "bidirectional"))
      (node (ref "C21") (pin "2") (pinfunction "2_2") (pintype "bidirectional"))
      (node (ref "C3") (pin "1") (pinfunction "1_1") (pintype "bidirectional"))
      (node (ref "C4") (pin "1") (pinfunction "1_1") (pintype "bidirectional"))
      (node (ref "C48") (pin "2") (pinfunction "2_2") (pintype "bidirectional"))
      (node (ref "C5") (pin "2") (pinfunction "2_2") (pintype "bidirectional"))
      (node (ref "R11") (pin "2") (pinfunction "2_2") (pintype "bidirectional"))
      (node (ref "R13") (pin "2") (pinfunction "2_2") (pintype "bidirectional"))
      (node (ref "R7") (pin "2") (pinfunction "2_2") (pintype "bidirectional"))
      (node (ref "U1") (pin "5") (pinfunction "VOUT_5") (pintype "bidirectional"))
      (node (ref "U13") (pin "15") (pinfunction "VCCTX_15") (pintype "bidirectional"))
      (node (ref "U13") (pin "19") (pinfunction "VCCRX_19") (pintype "bidirectional"))
      (node (ref "U13") (pin "20") (pinfunction "VCCPLL_20") (pintype "bidirectional"))
      (node (ref "U13") (pin "25") (pinfunction "VCCOSC_25") (pintype "bidirectional"))
      (node (ref "U13") (pin "28") (pinfunction "VCC_28") (pintype "bidirectional"))
      (node (ref "U2") (pin "1") (pinfunction "VCC_1_1") (pintype "bidirectional"))
      (node (ref "U2") (pin "17") (pinfunction "VCC_17_17") (pintype "bidirectional"))
      (node (ref "U2") (pin "5") (pinfunction "VCCA_5") (pintype "bidirectional"))
      (node (ref "U3") (pin "1") (pinfunction "VCC_1_1") (pintype "bidirectional"))
      (node (ref "U3") (pin "17") (pinfunction "VCC_17_17") (pintype "bidirectional"))
      (node (ref "U3") (pin "5") (pinfunction "VCCA_5") (pintype "bidirectional"))
    )
    (net (code "58") (name "unconnected-(J1-PadGNDBREAK)") (class "Default")
      (node (ref "J1") (pin "GNDBREAK") (pinfunction "GNDBREAK_GNDBREAK") (pintype "bidirectional"))
    )
    (net (code "59") (name "unconnected-(J8-P5{slash}CT-Pad5)") (class "Default")
      (node (ref "J8") (pin "5") (pinfunction "P5/CT_5") (pintype "bidirectional"))
    )
    (net (code "60") (name "unconnected-(P3-Pad3)") (class "Default")
      (node (ref "P3") (pin "3") (pinfunction "3_3") (pintype "bidirectional"))
    )
    (net (code "61") (name "unconnected-(P3-Pad4)") (class "Default")
      (node (ref "P3") (pin "4") (pinfunction "4_4") (pintype "bidirectional"))
    )
    (net (code "62") (name "unconnected-(P3-Pad5)") (class "Default")
      (node (ref "P3") (pin "5") (pinfunction "5_5") (pintype "bidirectional"))
    )
    (net (code "63") (name "unconnected-(P3-Pad6)") (class "Default")
      (node (ref "P3") (pin "6") (pinfunction "6_6") (pintype "bidirectional"))
    )
    (net (code "64") (name "unconnected-(P3-Pad7)") (class "Default")
      (node (ref "P3") (pin "7") (pinfunction "7_7") (pintype "bidirectional"))
    )
    (net (code "65") (name "unconnected-(P3-Pad8)") (class "Default")
      (node (ref "P3") (pin "8") (pinfunction "8_8") (pintype "bidirectional"))
    )
    (net (code "66") (name "unconnected-(P3-Pad9)") (class "Default")
      (node (ref "P3") (pin "9") (pinfunction "9_9") (pintype "bidirectional"))
    )
    (net (code "67") (name "unconnected-(P3-Pad10)") (class "Default")
      (node (ref "P3") (pin "10") (pinfunction "10_10") (pintype "bidirectional"))
    )
    (net (code "68") (name "unconnected-(P3-Pad11)") (class "Default")
      (node (ref "P3") (pin "11") (pinfunction "11_11") (pintype "bidirectional"))
    )
    (net (code "69") (name "unconnected-(P4-Pad3)") (class "Default")
      (node (ref "P4") (pin "3") (pinfunction "3_3") (pintype "bidirectional"))
    )
    (net (code "70") (name "unconnected-(P4-Pad4)") (class "Default")
      (node (ref "P4") (pin "4") (pinfunction "4_4") (pintype "bidirectional"))
    )
    (net (code "71") (name "unconnected-(P4-Pad5)") (class "Default")
      (node (ref "P4") (pin "5") (pinfunction "5_5") (pintype "bidirectional"))
    )
    (net (code "72") (name "unconnected-(P4-Pad6)") (class "Default")
      (node (ref "P4") (pin "6") (pinfunction "6_6") (pintype "bidirectional"))
    )
    (net (code "73") (name "unconnected-(P4-Pad7)") (class "Default")
      (node (ref "P4") (pin "7") (pinfunction "7_7") (pintype "bidirectional"))
    )
    (net (code "74") (name "unconnected-(P4-Pad8)") (class "Default")
      (node (ref "P4") (pin "8") (pinfunction "8_8") (pintype "bidirectional"))
    )
    (net (code "75") (name "unconnected-(P4-Pad9)") (class "Default")
      (node (ref "P4") (pin "9") (pinfunction "9_9") (pintype "bidirectional"))
    )
    (net (code "76") (name "unconnected-(P4-Pad10)") (class "Default")
      (node (ref "P4") (pin "10") (pinfunction "10_10") (pintype "bidirectional"))
    )
    (net (code "77") (name "unconnected-(P4-Pad11)") (class "Default")
      (node (ref "P4") (pin "11") (pinfunction "11_11") (pintype "bidirectional"))
    )
    (net (code "78") (name "unconnected-(U1-NC-Pad4)") (class "Default")
      (node (ref "U1") (pin "4") (pinfunction "NC_4") (pintype "bidirectional"))
    )
    (net (code "79") (name "unconnected-(U2-PB3-Pad26)") (class "Default")
      (node (ref "U2") (pin "26") (pinfunction "PB3_26") (pintype "bidirectional"))
    )
    (net (code "80") (name "unconnected-(U13-CLKOUT-Pad3)") (class "Default")
      (node (ref "U13") (pin "3") (pinfunction "CLKOUT_3") (pintype "bidirectional"))
    )
    (net (code "81") (name "unconnected-(U13-~{INT}-Pad4)") (class "Default")
      (node (ref "U13") (pin "4") (pinfunction "~{INT}_4") (pintype "bidirectional"))
    )
  )
)
